# Solid_State_Relay.net
KiCad netlist of a schematic drawn in Altium Designer
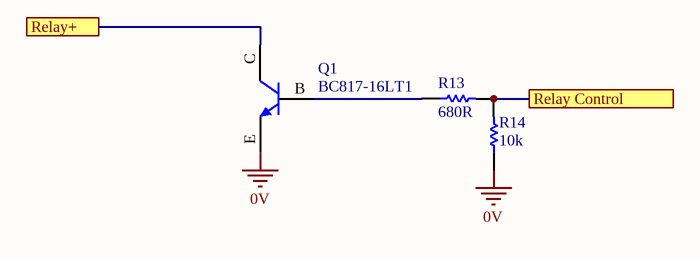
[diagram p0: Solid State Relay.SchDoc]

(export (version "E")
  (design (tool "Eeschema 10.0.6"))
  (components
    (comp (ref "Q1")
      (value "BC817-16LT1")
      (footprint "ON SOT-23 BJT")
      (description "300mW  BJT NPN Transistor")
      (fields
        (field (name "MANUFACTURER") "ON Semiconductor")
        (field (name "DIGIKEY PART NUMBER") "BC817-16LT1OSTR-ND")
      )
      (libsource (lib "ts_20-standard-library") (part "NPN"))
    )
    (comp (ref "R13")
      (value "680R")
      (footprint "0805")
      (fields
        (field (name "PART NUMBER") "RC0805FR07680RL")
        (field (name "MANUFACTURER") "YAGEO")
        (field (name "TOLERANCE") "0.01")
      )
      (libsource (lib "ts_20-standard-library") (part "Resistor"))
    )
    (comp (ref "R14")
      (value "10k")
      (footprint "0805")
      (fields
        (field (name "PART NUMBER") "RC0805FR0710KL")
        (field (name "MANUFACTURER") "YAGEO")
        (field (name "TOLERANCE") "0.01")
      )
      (libsource (lib "ts_20-standard-library") (part "Resistor"))
    )
  )
  (nets
    (net (code "1") (name "/Relay Control") (class "Default")
      (node (ref "R13") (pin "2") (pinfunction "2_2") (pintype "passive"))
      (node (ref "R14") (pin "2") (pinfunction "2_2") (pintype "passive"))
    )
    (net (code "2") (name "/Relay+") (class "Default")
      (node (ref "Q1") (pin "C") (pinfunction "C_C") (pintype "passive"))
    )
    (net (code "3") (name "0V") (class "Default")
      (node (ref "Q1") (pin "E") (pinfunction "E_E") (pintype "passive"))
      (node (ref "R14") (pin "1") (pinfunction "1_1") (pintype "passive"))
    )
    (net (code "4") (name "Net-(Q1-PadB)") (class "Default")
      (node (ref "Q1") (pin "B") (pinfunction "B_B") (pintype "passive"))
      (node (ref "R13") (pin "1") (pinfunction "1_1") (pintype "passive"))
    )
  )
)
